# schematic_nice.net
KiCad netlist of a schematic drawn in EAGLE
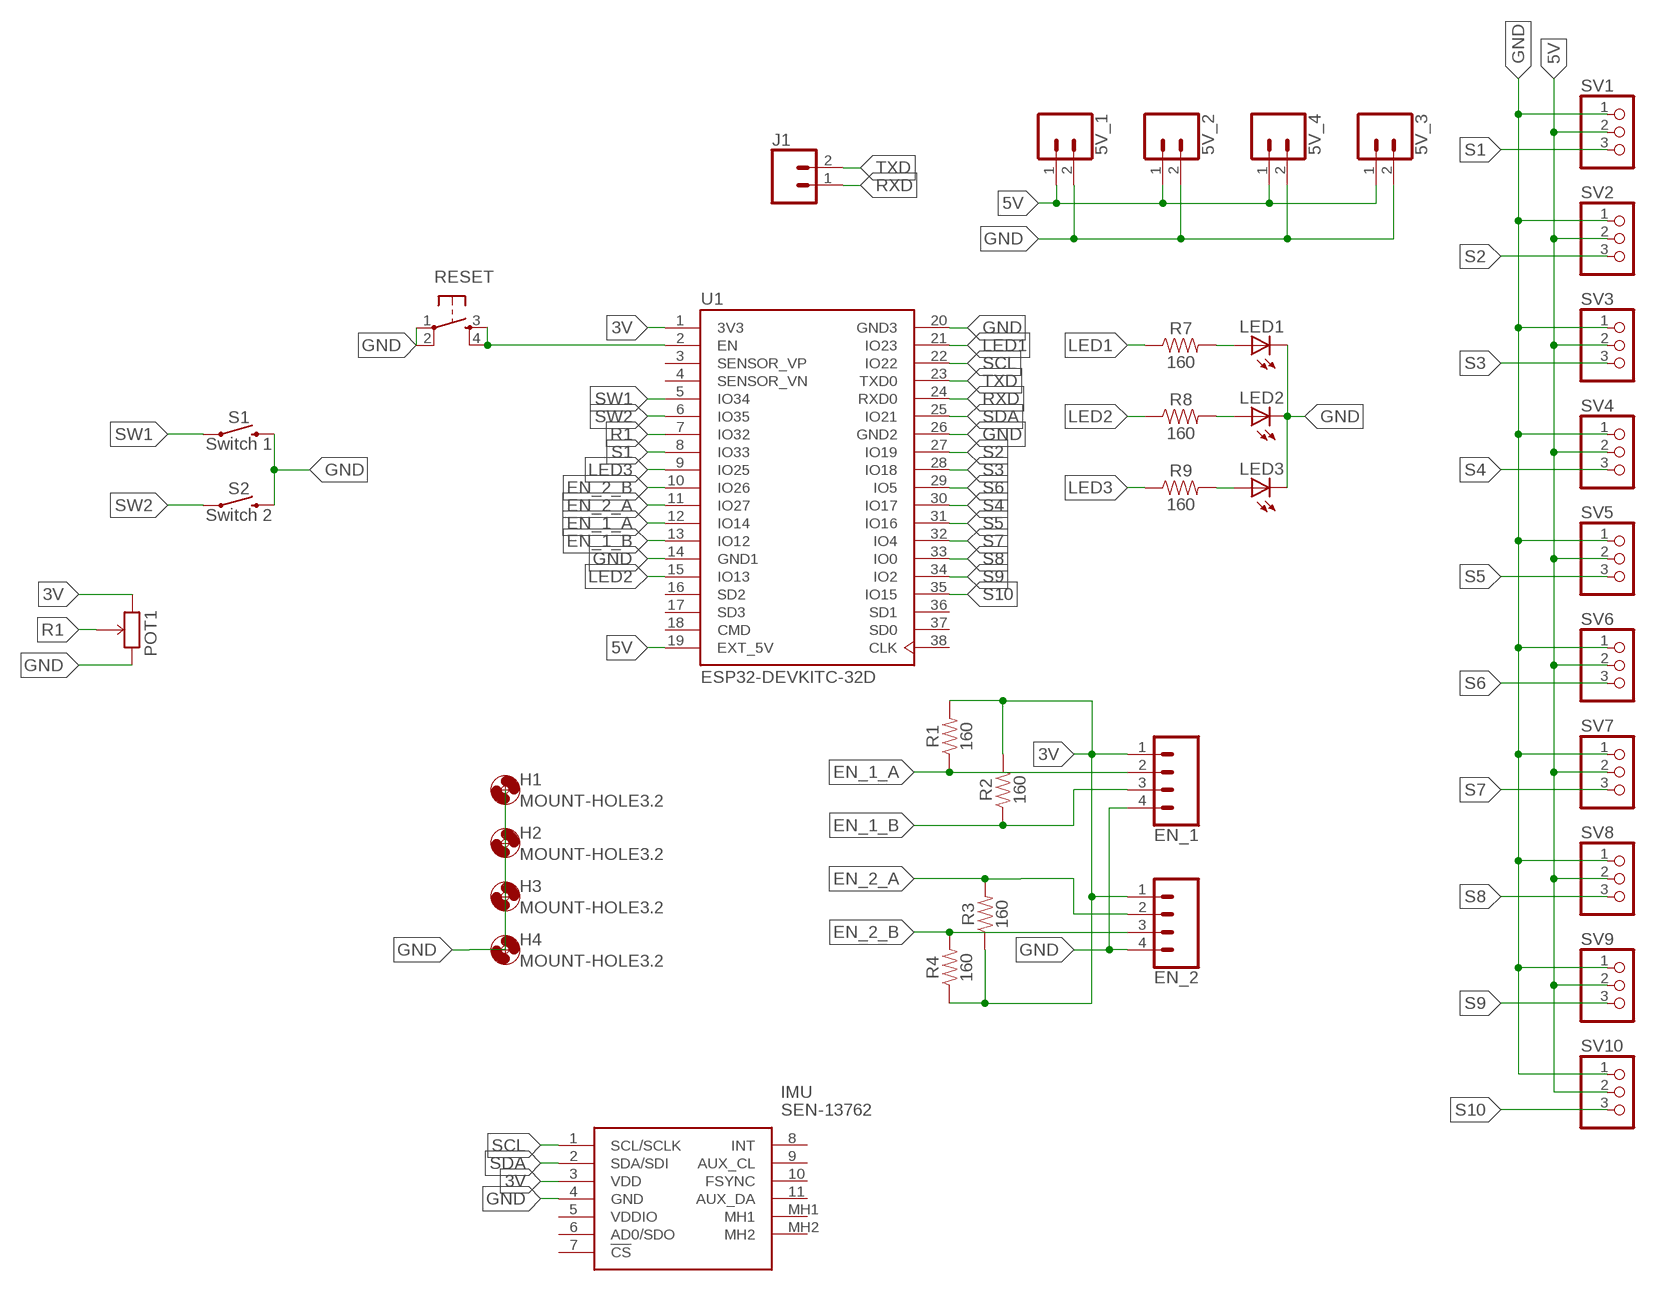
[diagram p0: schematic, sheet 1]

(export (version "E")
  (design (tool "Eeschema 10.0.6"))
  (components
    (comp (ref "5V_1")
      (value "CONN_02")
      (footprint "eagle-import:1X02")
      (libsource (lib "eagle-import") (part "CONN_02"))
    )
    (comp (ref "5V_2")
      (value "CONN_02")
      (footprint "eagle-import:1X02")
      (libsource (lib "eagle-import") (part "CONN_02"))
    )
    (comp (ref "5V_3")
      (value "CONN_02")
      (footprint "eagle-import:1X02")
      (libsource (lib "eagle-import") (part "CONN_02"))
    )
    (comp (ref "5V_4")
      (value "CONN_02")
      (footprint "eagle-import:1X02")
      (libsource (lib "eagle-import") (part "CONN_02"))
    )
    (comp (ref "EN_1")
      (value "CONN_04")
      (footprint "eagle-import:1X04")
      (libsource (lib "eagle-import") (part "CONN_04"))
    )
    (comp (ref "EN_2")
      (value "CONN_04")
      (footprint "eagle-import:1X04")
      (libsource (lib "eagle-import") (part "CONN_04"))
    )
    (comp (ref "H1")
      (value "MOUNT-HOLE3.2")
      (footprint "eagle-import:3,2")
      (libsource (lib "eagle-import") (part "MOUNT-HOLE3.2"))
    )
    (comp (ref "H2")
      (value "MOUNT-HOLE3.2")
      (footprint "eagle-import:3,2")
      (libsource (lib "eagle-import") (part "MOUNT-HOLE3.2"))
    )
    (comp (ref "H3")
      (value "MOUNT-HOLE3.2")
      (footprint "eagle-import:3,2")
      (libsource (lib "eagle-import") (part "MOUNT-HOLE3.2"))
    )
    (comp (ref "H4")
      (value "MOUNT-HOLE3.2")
      (footprint "eagle-import:3,2")
      (libsource (lib "eagle-import") (part "MOUNT-HOLE3.2"))
    )
    (comp (ref "IMU")
      (value "SEN-13762")
      (footprint "eagle-import:SEN13762")
      (libsource (lib "eagle-import") (part "SEN-13762"))
    )
    (comp (ref "J1")
      (value "CONN_02")
      (footprint "eagle-import:1X02")
      (libsource (lib "eagle-import") (part "CONN_02"))
    )
    (comp (ref "LED1")
      (value "LED3MM")
      (footprint "eagle-import:LED3MM")
      (libsource (lib "eagle-import") (part "LED3MM"))
    )
    (comp (ref "LED2")
      (value "LED3MM")
      (footprint "eagle-import:LED3MM")
      (libsource (lib "eagle-import") (part "LED3MM"))
    )
    (comp (ref "LED3")
      (value "LED3MM")
      (footprint "eagle-import:LED3MM")
      (libsource (lib "eagle-import") (part "LED3MM"))
    )
    (comp (ref "POT1")
      (value "POTENTIOMETER_THT")
      (footprint "eagle-import:POTENTIOMETER")
      (libsource (lib "eagle-import") (part "POTENTIOMETER_THT"))
    )
    (comp (ref "R1")
      (value "160")
      (footprint "eagle-import:AXIAL-0.3")
      (libsource (lib "eagle-import") (part "10KOHM-HORIZ-1/4W-1%"))
    )
    (comp (ref "R2")
      (value "160")
      (footprint "eagle-import:AXIAL-0.3")
      (libsource (lib "eagle-import") (part "10KOHM-HORIZ-1/4W-1%"))
    )
    (comp (ref "R3")
      (value "160")
      (footprint "eagle-import:AXIAL-0.3")
      (libsource (lib "eagle-import") (part "10KOHM-HORIZ-1/4W-1%"))
    )
    (comp (ref "R4")
      (value "160")
      (footprint "eagle-import:AXIAL-0.3")
      (libsource (lib "eagle-import") (part "10KOHM-HORIZ-1/4W-1%"))
    )
    (comp (ref "R7")
      (value "160")
      (footprint "eagle-import:AXIAL-0.3")
      (libsource (lib "eagle-import") (part "10KOHM-HORIZ-1/4W-1%"))
    )
    (comp (ref "R8")
      (value "160")
      (footprint "eagle-import:AXIAL-0.3")
      (libsource (lib "eagle-import") (part "10KOHM-HORIZ-1/4W-1%"))
    )
    (comp (ref "R9")
      (value "160")
      (footprint "eagle-import:AXIAL-0.3")
      (libsource (lib "eagle-import") (part "10KOHM-HORIZ-1/4W-1%"))
    )
    (comp (ref "RESET")
      (value "TAC_SWITCHPTH")
      (footprint "eagle-import:TACTILE-PTH")
      (libsource (lib "eagle-import") (part "TAC_SWITCHPTH"))
    )
    (comp (ref "S1")
      (value "Switch 1")
      (footprint "eagle-import:TACTILE_SWITCH_PTH_12MM")
      (libsource (lib "eagle-import") (part "MOMENTARY-SWITCH-SPST-PTH-12MM"))
    )
    (comp (ref "S2")
      (value "Switch 2")
      (footprint "eagle-import:TACTILE_SWITCH_PTH_12MM")
      (libsource (lib "eagle-import") (part "MOMENTARY-SWITCH-SPST-PTH-12MM"))
    )
    (comp (ref "SV1")
      (value "PINHD-1X3")
      (footprint "eagle-import:1X03")
      (libsource (lib "eagle-import") (part "PINHD-1X3"))
    )
    (comp (ref "SV2")
      (value "PINHD-1X3")
      (footprint "eagle-import:1X03")
      (libsource (lib "eagle-import") (part "PINHD-1X3"))
    )
    (comp (ref "SV3")
      (value "PINHD-1X3")
      (footprint "eagle-import:1X03")
      (libsource (lib "eagle-import") (part "PINHD-1X3"))
    )
    (comp (ref "SV4")
      (value "PINHD-1X3")
      (footprint "eagle-import:1X03")
      (libsource (lib "eagle-import") (part "PINHD-1X3"))
    )
    (comp (ref "SV5")
      (value "PINHD-1X3")
      (footprint "eagle-import:1X03")
      (libsource (lib "eagle-import") (part "PINHD-1X3"))
    )
    (comp (ref "SV6")
      (value "PINHD-1X3")
      (footprint "eagle-import:1X03")
      (libsource (lib "eagle-import") (part "PINHD-1X3"))
    )
    (comp (ref "SV7")
      (value "PINHD-1X3")
      (footprint "eagle-import:1X03")
      (libsource (lib "eagle-import") (part "PINHD-1X3"))
    )
    (comp (ref "SV8")
      (value "PINHD-1X3")
      (footprint "eagle-import:1X03")
      (libsource (lib "eagle-import") (part "PINHD-1X3"))
    )
    (comp (ref "SV9")
      (value "PINHD-1X3")
      (footprint "eagle-import:1X03")
      (libsource (lib "eagle-import") (part "PINHD-1X3"))
    )
    (comp (ref "SV10")
      (value "PINHD-1X3")
      (footprint "eagle-import:1X03")
      (libsource (lib "eagle-import") (part "PINHD-1X3"))
    )
    (comp (ref "U1")
      (value "ESP32-DEVKITC-32D")
      (footprint "eagle-import:MODULE_ESP32-DEVKITC-32D")
      (fields (field (name "MF") "Espressif Systems"))
      (libsource (lib "eagle-import") (part "ESP32-DEVKITC-32D"))
    )
  )
  (nets
    (net (code "1") (name "3V") (class "Default")
      (node (ref "EN_1") (pin "1") (pinfunction "1_1") (pintype "passive"))
      (node (ref "EN_2") (pin "1") (pinfunction "1_1") (pintype "passive"))
      (node (ref "IMU") (pin "3") (pinfunction "VDD_3") (pintype "bidirectional"))
      (node (ref "POT1") (pin "3") (pinfunction "CW_3") (pintype "passive"))
      (node (ref "R1") (pin "P$2") (pinfunction "2_P$2") (pintype "passive"))
      (node (ref "R2") (pin "P$2") (pinfunction "2_P$2") (pintype "passive"))
      (node (ref "R3") (pin "P$1") (pinfunction "1_P$1") (pintype "passive"))
      (node (ref "R4") (pin "P$1") (pinfunction "1_P$1") (pintype "passive"))
      (node (ref "U1") (pin "1") (pinfunction "3V3_1") (pintype "power_in"))
    )
    (net (code "2") (name "5V") (class "Default")
      (node (ref "5V_1") (pin "1") (pinfunction "1_1") (pintype "passive"))
      (node (ref "5V_2") (pin "1") (pinfunction "1_1") (pintype "passive"))
      (node (ref "5V_3") (pin "1") (pinfunction "1_1") (pintype "passive"))
      (node (ref "5V_4") (pin "1") (pinfunction "1_1") (pintype "passive"))
      (node (ref "SV1") (pin "2") (pinfunction "2_2") (pintype "passive"))
      (node (ref "SV10") (pin "2") (pinfunction "2_2") (pintype "passive"))
      (node (ref "SV2") (pin "2") (pinfunction "2_2") (pintype "passive"))
      (node (ref "SV3") (pin "2") (pinfunction "2_2") (pintype "passive"))
      (node (ref "SV4") (pin "2") (pinfunction "2_2") (pintype "passive"))
      (node (ref "SV5") (pin "2") (pinfunction "2_2") (pintype "passive"))
      (node (ref "SV6") (pin "2") (pinfunction "2_2") (pintype "passive"))
      (node (ref "SV7") (pin "2") (pinfunction "2_2") (pintype "passive"))
      (node (ref "SV8") (pin "2") (pinfunction "2_2") (pintype "passive"))
      (node (ref "SV9") (pin "2") (pinfunction "2_2") (pintype "passive"))
      (node (ref "U1") (pin "19") (pinfunction "EXT_5V_19") (pintype "power_in"))
    )
    (net (code "3") (name "EN_1_A") (class "Default")
      (node (ref "EN_1") (pin "2") (pinfunction "2_2") (pintype "passive"))
      (node (ref "R1") (pin "P$1") (pinfunction "1_P$1") (pintype "passive"))
      (node (ref "U1") (pin "12") (pinfunction "IO14_12") (pintype "bidirectional"))
    )
    (net (code "4") (name "EN_1_B") (class "Default")
      (node (ref "EN_1") (pin "3") (pinfunction "3_3") (pintype "passive"))
      (node (ref "R2") (pin "P$1") (pinfunction "1_P$1") (pintype "passive"))
      (node (ref "U1") (pin "13") (pinfunction "IO12_13") (pintype "bidirectional"))
    )
    (net (code "5") (name "EN_2_A") (class "Default")
      (node (ref "EN_2") (pin "2") (pinfunction "2_2") (pintype "passive"))
      (node (ref "R3") (pin "P$2") (pinfunction "2_P$2") (pintype "passive"))
      (node (ref "U1") (pin "11") (pinfunction "IO27_11") (pintype "bidirectional"))
    )
    (net (code "6") (name "EN_2_B") (class "Default")
      (node (ref "EN_2") (pin "3") (pinfunction "3_3") (pintype "passive"))
      (node (ref "R4") (pin "P$2") (pinfunction "2_P$2") (pintype "passive"))
      (node (ref "U1") (pin "10") (pinfunction "IO26_10") (pintype "bidirectional"))
    )
    (net (code "7") (name "GND") (class "Default")
      (node (ref "5V_1") (pin "2") (pinfunction "2_2") (pintype "passive"))
      (node (ref "5V_2") (pin "2") (pinfunction "2_2") (pintype "passive"))
      (node (ref "5V_3") (pin "2") (pinfunction "2_2") (pintype "passive"))
      (node (ref "5V_4") (pin "2") (pinfunction "2_2") (pintype "passive"))
      (node (ref "EN_1") (pin "4") (pinfunction "4_4") (pintype "passive"))
      (node (ref "EN_2") (pin "4") (pinfunction "4_4") (pintype "passive"))
      (node (ref "IMU") (pin "4") (pinfunction "GND_4") (pintype "bidirectional"))
      (node (ref "LED1") (pin "K") (pinfunction "C_K") (pintype "passive"))
      (node (ref "LED2") (pin "K") (pinfunction "C_K") (pintype "passive"))
      (node (ref "LED3") (pin "K") (pinfunction "C_K") (pintype "passive"))
      (node (ref "POT1") (pin "1") (pinfunction "CCW_1") (pintype "passive"))
      (node (ref "RESET") (pin "1") (pinfunction "1_1") (pintype "passive"))
      (node (ref "RESET") (pin "2") (pinfunction "2_2") (pintype "passive"))
      (node (ref "S1") (pin "3") (pinfunction "2_3") (pintype "passive"))
      (node (ref "S2") (pin "3") (pinfunction "2_3") (pintype "passive"))
      (node (ref "SV1") (pin "1") (pinfunction "1_1") (pintype "passive"))
      (node (ref "SV10") (pin "1") (pinfunction "1_1") (pintype "passive"))
      (node (ref "SV2") (pin "1") (pinfunction "1_1") (pintype "passive"))
      (node (ref "SV3") (pin "1") (pinfunction "1_1") (pintype "passive"))
      (node (ref "SV4") (pin "1") (pinfunction "1_1") (pintype "passive"))
      (node (ref "SV5") (pin "1") (pinfunction "1_1") (pintype "passive"))
      (node (ref "SV6") (pin "1") (pinfunction "1_1") (pintype "passive"))
      (node (ref "SV7") (pin "1") (pinfunction "1_1") (pintype "passive"))
      (node (ref "SV8") (pin "1") (pinfunction "1_1") (pintype "passive"))
      (node (ref "SV9") (pin "1") (pinfunction "1_1") (pintype "passive"))
      (node (ref "U1") (pin "14") (pinfunction "GND1_14") (pintype "power_in"))
      (node (ref "U1") (pin "20") (pinfunction "GND3_20") (pintype "power_in"))
      (node (ref "U1") (pin "26") (pinfunction "GND2_26") (pintype "power_in"))
    )
    (net (code "8") (name "LED1") (class "Default")
      (node (ref "R7") (pin "P$1") (pinfunction "1_P$1") (pintype "passive"))
      (node (ref "U1") (pin "21") (pinfunction "IO23_21") (pintype "bidirectional"))
    )
    (net (code "9") (name "LED2") (class "Default")
      (node (ref "R8") (pin "P$1") (pinfunction "1_P$1") (pintype "passive"))
      (node (ref "U1") (pin "15") (pinfunction "IO13_15") (pintype "bidirectional"))
    )
    (net (code "10") (name "LED3") (class "Default")
      (node (ref "R9") (pin "P$1") (pinfunction "1_P$1") (pintype "passive"))
      (node (ref "U1") (pin "9") (pinfunction "IO25_9") (pintype "bidirectional"))
    )
    (net (code "11") (name "Net-(R7-2)") (class "Default")
      (node (ref "LED1") (pin "A") (pinfunction "A_A") (pintype "passive"))
      (node (ref "R7") (pin "P$2") (pinfunction "2_P$2") (pintype "passive"))
    )
    (net (code "12") (name "Net-(R8-2)") (class "Default")
      (node (ref "LED2") (pin "A") (pinfunction "A_A") (pintype "passive"))
      (node (ref "R8") (pin "P$2") (pinfunction "2_P$2") (pintype "passive"))
    )
    (net (code "13") (name "Net-(R9-2)") (class "Default")
      (node (ref "LED3") (pin "A") (pinfunction "A_A") (pintype "passive"))
      (node (ref "R9") (pin "P$2") (pinfunction "2_P$2") (pintype "passive"))
    )
    (net (code "14") (name "Net-(U1-EN)") (class "Default")
      (node (ref "RESET") (pin "3") (pinfunction "3_3") (pintype "passive"))
      (node (ref "RESET") (pin "4") (pinfunction "4_4") (pintype "passive"))
      (node (ref "U1") (pin "2") (pinfunction "EN_2") (pintype "input"))
    )
    (net (code "15") (name "R1") (class "Default")
      (node (ref "POT1") (pin "2") (pinfunction "WIPER_2") (pintype "passive"))
      (node (ref "U1") (pin "7") (pinfunction "IO32_7") (pintype "bidirectional"))
    )
    (net (code "16") (name "RXD") (class "Default")
      (node (ref "J1") (pin "1") (pinfunction "1_1") (pintype "passive"))
      (node (ref "U1") (pin "24") (pinfunction "RXD0_24") (pintype "input"))
    )
    (net (code "17") (name "S1") (class "Default")
      (node (ref "SV1") (pin "3") (pinfunction "3_3") (pintype "passive"))
      (node (ref "U1") (pin "8") (pinfunction "IO33_8") (pintype "bidirectional"))
    )
    (net (code "18") (name "S2") (class "Default")
      (node (ref "SV2") (pin "3") (pinfunction "3_3") (pintype "passive"))
      (node (ref "U1") (pin "27") (pinfunction "IO19_27") (pintype "bidirectional"))
    )
    (net (code "19") (name "S3") (class "Default")
      (node (ref "SV3") (pin "3") (pinfunction "3_3") (pintype "passive"))
      (node (ref "U1") (pin "28") (pinfunction "IO18_28") (pintype "bidirectional"))
    )
    (net (code "20") (name "S4") (class "Default")
      (node (ref "SV4") (pin "3") (pinfunction "3_3") (pintype "passive"))
      (node (ref "U1") (pin "30") (pinfunction "IO17_30") (pintype "bidirectional"))
    )
    (net (code "21") (name "S5") (class "Default")
      (node (ref "SV5") (pin "3") (pinfunction "3_3") (pintype "passive"))
      (node (ref "U1") (pin "31") (pinfunction "IO16_31") (pintype "bidirectional"))
    )
    (net (code "22") (name "S6") (class "Default")
      (node (ref "SV6") (pin "3") (pinfunction "3_3") (pintype "passive"))
      (node (ref "U1") (pin "29") (pinfunction "IO5_29") (pintype "bidirectional"))
    )
    (net (code "23") (name "S7") (class "Default")
      (node (ref "SV7") (pin "3") (pinfunction "3_3") (pintype "passive"))
      (node (ref "U1") (pin "32") (pinfunction "IO4_32") (pintype "bidirectional"))
    )
    (net (code "24") (name "S8") (class "Default")
      (node (ref "SV8") (pin "3") (pinfunction "3_3") (pintype "passive"))
      (node (ref "U1") (pin "33") (pinfunction "IO0_33") (pintype "bidirectional"))
    )
    (net (code "25") (name "S9") (class "Default")
      (node (ref "SV9") (pin "3") (pinfunction "3_3") (pintype "passive"))
      (node (ref "U1") (pin "34") (pinfunction "IO2_34") (pintype "bidirectional"))
    )
    (net (code "26") (name "S10") (class "Default")
      (node (ref "SV10") (pin "3") (pinfunction "3_3") (pintype "passive"))
      (node (ref "U1") (pin "35") (pinfunction "IO15_35") (pintype "bidirectional"))
    )
    (net (code "27") (name "SCL") (class "Default")
      (node (ref "IMU") (pin "1") (pinfunction "SCL/SCLK_1") (pintype "bidirectional"))
      (node (ref "U1") (pin "22") (pinfunction "IO22_22") (pintype "bidirectional"))
    )
    (net (code "28") (name "SDA") (class "Default")
      (node (ref "IMU") (pin "2") (pinfunction "SDA/SDI_2") (pintype "bidirectional"))
      (node (ref "U1") (pin "25") (pinfunction "IO21_25") (pintype "bidirectional"))
    )
    (net (code "29") (name "SW1") (class "Default")
      (node (ref "S1") (pin "1") (pinfunction "1_1") (pintype "passive"))
      (node (ref "U1") (pin "5") (pinfunction "IO34_5") (pintype "bidirectional"))
    )
    (net (code "30") (name "SW2") (class "Default")
      (node (ref "S2") (pin "1") (pinfunction "1_1") (pintype "passive"))
      (node (ref "U1") (pin "6") (pinfunction "IO35_6") (pintype "bidirectional"))
    )
    (net (code "31") (name "TXD") (class "Default")
      (node (ref "J1") (pin "2") (pinfunction "2_2") (pintype "passive"))
      (node (ref "U1") (pin "23") (pinfunction "TXD0_23") (pintype "output"))
    )
    (net (code "32") (name "unconnected-(IMU-AD0{slash}SDO-Pad6)") (class "Default")
      (node (ref "IMU") (pin "6") (pinfunction "AD0/SDO_6") (pintype "bidirectional"))
    )
    (net (code "33") (name "unconnected-(IMU-AUX_CL-Pad9)") (class "Default")
      (node (ref "IMU") (pin "9") (pinfunction "AUX_CL_9") (pintype "bidirectional"))
    )
    (net (code "34") (name "unconnected-(IMU-AUX_DA-Pad11)") (class "Default")
      (node (ref "IMU") (pin "11") (pinfunction "AUX_DA_11") (pintype "bidirectional"))
    )
    (net (code "35") (name "unconnected-(IMU-FSYNC-Pad10)") (class "Default")
      (node (ref "IMU") (pin "10") (pinfunction "FSYNC_10") (pintype "bidirectional"))
    )
    (net (code "36") (name "unconnected-(IMU-INT-Pad8)") (class "Default")
      (node (ref "IMU") (pin "8") (pinfunction "INT_8") (pintype "bidirectional"))
    )
    (net (code "37") (name "unconnected-(IMU-PadMH1)") (class "Default")
      (node (ref "IMU") (pin "MH1") (pinfunction "MH1_MH1") (pintype "bidirectional"))
    )
    (net (code "38") (name "unconnected-(IMU-PadMH2)") (class "Default")
      (node (ref "IMU") (pin "MH2") (pinfunction "MH2_MH2") (pintype "bidirectional"))
    )
    (net (code "39") (name "unconnected-(IMU-VDDIO-Pad5)") (class "Default")
      (node (ref "IMU") (pin "5") (pinfunction "VDDIO_5") (pintype "bidirectional"))
    )
    (net (code "40") (name "unconnected-(IMU-~{CS}-Pad7)") (class "Default")
      (node (ref "IMU") (pin "7") (pinfunction "~{CS}_7") (pintype "bidirectional"))
    )
    (net (code "41") (name "unconnected-(U1-CLK-Pad38)") (class "Default")
      (node (ref "U1") (pin "38") (pinfunction "CLK_38") (pintype "input"))
    )
    (net (code "42") (name "unconnected-(U1-CMD-Pad18)") (class "Default")
      (node (ref "U1") (pin "18") (pinfunction "CMD_18") (pintype "bidirectional"))
    )
    (net (code "43") (name "unconnected-(U1-SD0-Pad37)") (class "Default")
      (node (ref "U1") (pin "37") (pinfunction "SD0_37") (pintype "bidirectional"))
    )
    (net (code "44") (name "unconnected-(U1-SD1-Pad36)") (class "Default")
      (node (ref "U1") (pin "36") (pinfunction "SD1_36") (pintype "bidirectional"))
    )
    (net (code "45") (name "unconnected-(U1-SD2-Pad16)") (class "Default")
      (node (ref "U1") (pin "16") (pinfunction "SD2_16") (pintype "bidirectional"))
    )
    (net (code "46") (name "unconnected-(U1-SD3-Pad17)") (class "Default")
      (node (ref "U1") (pin "17") (pinfunction "SD3_17") (pintype "bidirectional"))
    )
    (net (code "47") (name "unconnected-(U1-SENSOR_VN-Pad4)") (class "Default")
      (node (ref "U1") (pin "4") (pinfunction "SENSOR_VN_4") (pintype "input"))
    )
    (net (code "48") (name "unconnected-(U1-SENSOR_VP-Pad3)") (class "Default")
      (node (ref "U1") (pin "3") (pinfunction "SENSOR_VP_3") (pintype "input"))
    )
  )
)
